# TRV_SX1231_V0_1a.net
KiCad netlist of a schematic drawn in EAGLE
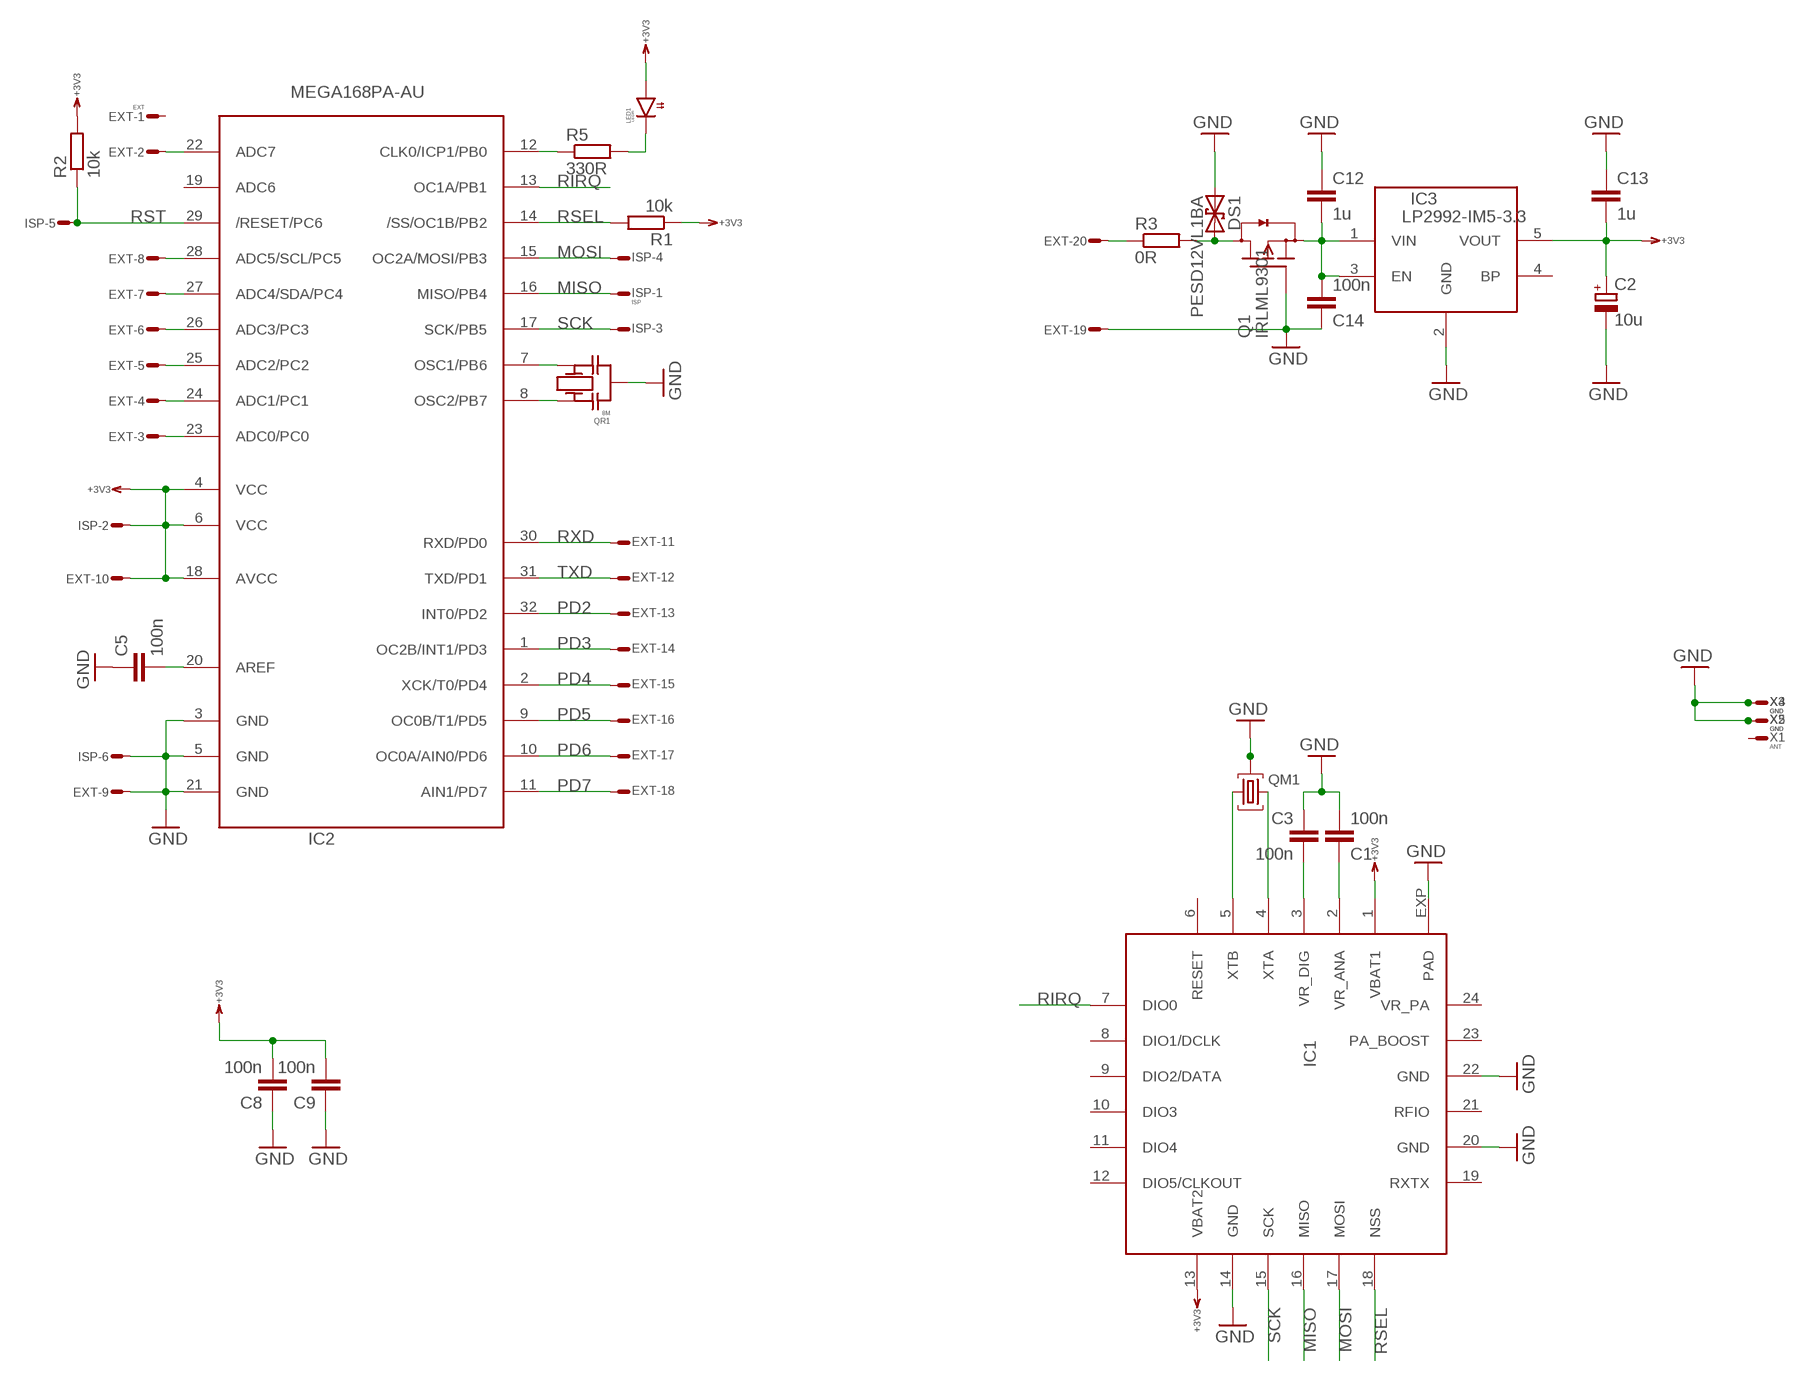
[diagram p0: schematic, sheet 1]

(export (version "E")
  (design (tool "Eeschema 10.0.6"))
  (components
    (comp (ref "C1")
      (value "100n")
      (footprint "eagle-import:0603")
      (libsource (lib "eagle-import") (part "C0603"))
    )
    (comp (ref "C2")
      (value "10u")
      (footprint "eagle-import:SMC_B")
      (libsource (lib "eagle-import") (part "C_POLSMCB"))
    )
    (comp (ref "C3")
      (value "100n")
      (footprint "eagle-import:0603")
      (libsource (lib "eagle-import") (part "C0603"))
    )
    (comp (ref "C5")
      (value "100n")
      (footprint "eagle-import:0603")
      (libsource (lib "eagle-import") (part "C0603"))
    )
    (comp (ref "C8")
      (value "100n")
      (footprint "eagle-import:0603")
      (libsource (lib "eagle-import") (part "C0603"))
    )
    (comp (ref "C9")
      (value "100n")
      (footprint "eagle-import:0603")
      (libsource (lib "eagle-import") (part "C0603"))
    )
    (comp (ref "C12")
      (value "1u")
      (footprint "eagle-import:0603")
      (libsource (lib "eagle-import") (part "C0603"))
    )
    (comp (ref "C13")
      (value "1u")
      (footprint "eagle-import:0603")
      (libsource (lib "eagle-import") (part "C0603"))
    )
    (comp (ref "C14")
      (value "100n")
      (footprint "eagle-import:0603")
      (libsource (lib "eagle-import") (part "C0603"))
    )
    (comp (ref "DS1")
      (value "PESD12VL1BA")
      (footprint "eagle-import:SOD323")
      (libsource (lib "eagle-import") (part "TVS-U323"))
    )
    (comp (ref "EXT")
      (value "EXT")
      (footprint "eagle-import:ML20S")
      (libsource (lib "eagle-import") (part "ML20?ES"))
    )
    (comp (ref "IC1")
      (value "SX1231")
      (footprint "eagle-import:QFN24")
      (libsource (lib "eagle-import") (part "SX1231"))
    )
    (comp (ref "IC2")
      (value "MEGA168PA-AU")
      (footprint "eagle-import:TQFP32-08")
      (libsource (lib "eagle-import") (part "MEGA168PA"))
    )
    (comp (ref "IC3")
      (value "LP2992-IM5-3.3")
      (footprint "eagle-import:SOT23-5")
      (libsource (lib "eagle-import") (part "LDO"))
    )
    (comp (ref "ISP")
      (value "ISP")
      (footprint "eagle-import:ML6S")
      (libsource (lib "eagle-import") (part "ML6ES"))
    )
    (comp (ref "LED1")
      (value "LEDR")
      (footprint "eagle-import:0805")
      (libsource (lib "eagle-import") (part "LED0805"))
    )
    (comp (ref "Q1")
      (value "IRLML9301")
      (footprint "eagle-import:SOT23")
      (libsource (lib "eagle-import") (part "FET-PDSOT23"))
    )
    (comp (ref "QM1")
      (value "QM5X3.2")
      (footprint "eagle-import:ABM3C")
      (libsource (lib "eagle-import") (part "QM5X3.2"))
    )
    (comp (ref "QR1")
      (value "8M")
      (footprint "eagle-import:CR")
      (libsource (lib "eagle-import") (part "QRCR"))
    )
    (comp (ref "R1")
      (value "10k")
      (footprint "eagle-import:0603")
      (libsource (lib "eagle-import") (part "R0603"))
    )
    (comp (ref "R2")
      (value "10k")
      (footprint "eagle-import:0603")
      (libsource (lib "eagle-import") (part "R0603"))
    )
    (comp (ref "R3")
      (value "0R")
      (footprint "eagle-import:0603")
      (libsource (lib "eagle-import") (part "R0603"))
    )
    (comp (ref "R5")
      (value "330R")
      (footprint "eagle-import:0603")
      (libsource (lib "eagle-import") (part "R0603"))
    )
    (comp (ref "X1")
      (value "ANT")
      (footprint "eagle-import:S2.54_1.27")
      (libsource (lib "eagle-import") (part "WIREPADS2.54/1.27"))
    )
    (comp (ref "X2")
      (value "GND")
      (footprint "eagle-import:S2.54_1.27")
      (libsource (lib "eagle-import") (part "WIREPADS2.54/1.27"))
    )
    (comp (ref "X3")
      (value "GND")
      (footprint "eagle-import:S2.54_1.27")
      (libsource (lib "eagle-import") (part "WIREPADS2.54/1.27"))
    )
    (comp (ref "X4")
      (value "GND")
      (footprint "eagle-import:S2.54_1.27")
      (libsource (lib "eagle-import") (part "WIREPADS2.54/1.27"))
    )
    (comp (ref "X5")
      (value "GND")
      (footprint "eagle-import:S2.54_1.27")
      (libsource (lib "eagle-import") (part "WIREPADS2.54/1.27"))
    )
  )
  (nets
    (net (code "1") (name "+3V3") (class "Default")
      (node (ref "C13") (pin "2") (pinfunction "2_2") (pintype "passive"))
      (node (ref "C2") (pin "+") (pinfunction "+_+") (pintype "passive"))
      (node (ref "C8") (pin "2") (pinfunction "2_2") (pintype "passive"))
      (node (ref "C9") (pin "2") (pinfunction "2_2") (pintype "passive"))
      (node (ref "EXT") (pin "10") (pinfunction "S_10") (pintype "passive"))
      (node (ref "IC1") (pin "1") (pinfunction "VBAT1_1") (pintype "bidirectional"))
      (node (ref "IC1") (pin "13") (pinfunction "VBAT2_13") (pintype "bidirectional"))
      (node (ref "IC2") (pin "18") (pinfunction "AVCC_18") (pintype "bidirectional"))
      (node (ref "IC2") (pin "4") (pinfunction "VCC_4") (pintype "bidirectional"))
      (node (ref "IC2") (pin "6") (pinfunction "VCC_6") (pintype "bidirectional"))
      (node (ref "IC3") (pin "5") (pinfunction "VOUT_5") (pintype "bidirectional"))
      (node (ref "ISP") (pin "2") (pinfunction "S_2") (pintype "passive"))
      (node (ref "LED1") (pin "C") (pinfunction "A_C") (pintype "bidirectional"))
      (node (ref "R1") (pin "1") (pinfunction "1_1") (pintype "passive"))
      (node (ref "R2") (pin "2") (pinfunction "2_2") (pintype "passive"))
    )
    (net (code "2") (name "/MISO") (class "Default")
      (node (ref "IC1") (pin "16") (pinfunction "MISO_16") (pintype "output"))
      (node (ref "IC2") (pin "16") (pinfunction "MISO/PB4_16") (pintype "bidirectional"))
      (node (ref "ISP") (pin "1") (pinfunction "S_1") (pintype "passive"))
    )
    (net (code "3") (name "/MOSI") (class "Default")
      (node (ref "IC1") (pin "17") (pinfunction "MOSI_17") (pintype "input"))
      (node (ref "IC2") (pin "15") (pinfunction "OC2A/MOSI/PB3_15") (pintype "bidirectional"))
      (node (ref "ISP") (pin "4") (pinfunction "S_4") (pintype "passive"))
    )
    (net (code "4") (name "/PD2") (class "Default")
      (node (ref "EXT") (pin "13") (pinfunction "S_13") (pintype "passive"))
      (node (ref "IC2") (pin "32") (pinfunction "INT0/PD2_32") (pintype "bidirectional"))
    )
    (net (code "5") (name "/PD3") (class "Default")
      (node (ref "EXT") (pin "14") (pinfunction "S_14") (pintype "passive"))
      (node (ref "IC2") (pin "1") (pinfunction "OC2B/INT1/PD3_1") (pintype "bidirectional"))
    )
    (net (code "6") (name "/PD4") (class "Default")
      (node (ref "EXT") (pin "15") (pinfunction "S_15") (pintype "passive"))
      (node (ref "IC2") (pin "2") (pinfunction "XCK/T0/PD4_2") (pintype "bidirectional"))
    )
    (net (code "7") (name "/PD5") (class "Default")
      (node (ref "EXT") (pin "16") (pinfunction "S_16") (pintype "passive"))
      (node (ref "IC2") (pin "9") (pinfunction "OC0B/T1/PD5_9") (pintype "bidirectional"))
    )
    (net (code "8") (name "/PD6") (class "Default")
      (node (ref "EXT") (pin "17") (pinfunction "S_17") (pintype "passive"))
      (node (ref "IC2") (pin "10") (pinfunction "OC0A/AIN0/PD6_10") (pintype "bidirectional"))
    )
    (net (code "9") (name "/PD7") (class "Default")
      (node (ref "EXT") (pin "18") (pinfunction "S_18") (pintype "passive"))
      (node (ref "IC2") (pin "11") (pinfunction "AIN1/PD7_11") (pintype "bidirectional"))
    )
    (net (code "10") (name "/RIRQ") (class "Default")
      (node (ref "IC1") (pin "7") (pinfunction "DIO0_7") (pintype "bidirectional"))
      (node (ref "IC2") (pin "13") (pinfunction "OC1A/PB1_13") (pintype "bidirectional"))
    )
    (net (code "11") (name "/RSEL") (class "Default")
      (node (ref "IC1") (pin "18") (pinfunction "NSS_18") (pintype "input"))
      (node (ref "IC2") (pin "14") (pinfunction "/SS/OC1B/PB2_14") (pintype "bidirectional"))
      (node (ref "R1") (pin "2") (pinfunction "2_2") (pintype "passive"))
    )
    (net (code "12") (name "/RST") (class "Default")
      (node (ref "IC2") (pin "29") (pinfunction "/RESET/PC6_29") (pintype "bidirectional"))
      (node (ref "ISP") (pin "5") (pinfunction "S_5") (pintype "passive"))
      (node (ref "R2") (pin "1") (pinfunction "1_1") (pintype "passive"))
    )
    (net (code "13") (name "/RXD") (class "Default")
      (node (ref "EXT") (pin "11") (pinfunction "S_11") (pintype "passive"))
      (node (ref "IC2") (pin "30") (pinfunction "RXD/PD0_30") (pintype "bidirectional"))
    )
    (net (code "14") (name "/SCK") (class "Default")
      (node (ref "IC1") (pin "15") (pinfunction "SCK_15") (pintype "input"))
      (node (ref "IC2") (pin "17") (pinfunction "SCK/PB5_17") (pintype "bidirectional"))
      (node (ref "ISP") (pin "3") (pinfunction "S_3") (pintype "passive"))
    )
    (net (code "15") (name "/TXD") (class "Default")
      (node (ref "EXT") (pin "12") (pinfunction "S_12") (pintype "passive"))
      (node (ref "IC2") (pin "31") (pinfunction "TXD/PD1_31") (pintype "bidirectional"))
    )
    (net (code "16") (name "GND") (class "Default")
      (node (ref "C1") (pin "2") (pinfunction "2_2") (pintype "passive"))
      (node (ref "C12") (pin "1") (pinfunction "1_1") (pintype "passive"))
      (node (ref "C13") (pin "1") (pinfunction "1_1") (pintype "passive"))
      (node (ref "C14") (pin "1") (pinfunction "1_1") (pintype "passive"))
      (node (ref "C2") (pin "-") (pinfunction "-_-") (pintype "passive"))
      (node (ref "C3") (pin "1") (pinfunction "1_1") (pintype "passive"))
      (node (ref "C5") (pin "1") (pinfunction "1_1") (pintype "passive"))
      (node (ref "C8") (pin "1") (pinfunction "1_1") (pintype "passive"))
      (node (ref "C9") (pin "1") (pinfunction "1_1") (pintype "passive"))
      (node (ref "DS1") (pin "A") (pinfunction "1_A") (pintype "passive"))
      (node (ref "EXT") (pin "19") (pinfunction "S_19") (pintype "passive"))
      (node (ref "EXT") (pin "9") (pinfunction "S_9") (pintype "passive"))
      (node (ref "IC1") (pin "14") (pinfunction "GND_14") (pintype "bidirectional"))
      (node (ref "IC1") (pin "20") (pinfunction "GND_20") (pintype "bidirectional"))
      (node (ref "IC1") (pin "22") (pinfunction "GND_22") (pintype "bidirectional"))
      (node (ref "IC1") (pin "EXP") (pinfunction "PAD_EXP") (pintype "bidirectional"))
      (node (ref "IC2") (pin "21") (pinfunction "GND_21") (pintype "bidirectional"))
      (node (ref "IC2") (pin "3") (pinfunction "GND_3") (pintype "bidirectional"))
      (node (ref "IC2") (pin "5") (pinfunction "GND_5") (pintype "bidirectional"))
      (node (ref "IC3") (pin "2") (pinfunction "GND_2") (pintype "bidirectional"))
      (node (ref "ISP") (pin "6") (pinfunction "S_6") (pintype "passive"))
      (node (ref "Q1") (pin "1") (pinfunction "G_1") (pintype "passive"))
      (node (ref "QM1") (pin "P$2") (pinfunction "M1_P$2") (pintype "passive"))
      (node (ref "QM1") (pin "P$4") (pinfunction "M2_P$4") (pintype "passive"))
      (node (ref "QR1") (pin "M") (pinfunction "M_M") (pintype "passive"))
      (node (ref "X2") (pin "1") (pinfunction "S_1") (pintype "passive"))
      (node (ref "X3") (pin "1") (pinfunction "S_1") (pintype "passive"))
      (node (ref "X4") (pin "1") (pinfunction "S_1") (pintype "passive"))
      (node (ref "X5") (pin "1") (pinfunction "S_1") (pintype "passive"))
    )
    (net (code "17") (name "Net-(DS1-2)") (class "Default")
      (node (ref "DS1") (pin "C") (pinfunction "2_C") (pintype "passive"))
      (node (ref "Q1") (pin "3") (pinfunction "D_3") (pintype "passive"))
      (node (ref "R3") (pin "2") (pinfunction "2_2") (pintype "passive"))
    )
    (net (code "18") (name "Net-(EXTL-S)") (class "Default")
      (node (ref "EXT") (pin "2") (pinfunction "S_2") (pintype "passive"))
      (node (ref "IC2") (pin "22") (pinfunction "ADC7_22") (pintype "bidirectional"))
    )
    (net (code "19") (name "Net-(EXTM-S)") (class "Default")
      (node (ref "EXT") (pin "20") (pinfunction "S_20") (pintype "passive"))
      (node (ref "R3") (pin "1") (pinfunction "1_1") (pintype "passive"))
    )
    (net (code "20") (name "Net-(EXTN-S)") (class "Default")
      (node (ref "EXT") (pin "3") (pinfunction "S_3") (pintype "passive"))
      (node (ref "IC2") (pin "23") (pinfunction "ADC0/PC0_23") (pintype "bidirectional"))
    )
    (net (code "21") (name "Net-(EXTO-S)") (class "Default")
      (node (ref "EXT") (pin "4") (pinfunction "S_4") (pintype "passive"))
      (node (ref "IC2") (pin "24") (pinfunction "ADC1/PC1_24") (pintype "bidirectional"))
    )
    (net (code "22") (name "Net-(EXTP-S)") (class "Default")
      (node (ref "EXT") (pin "5") (pinfunction "S_5") (pintype "passive"))
      (node (ref "IC2") (pin "25") (pinfunction "ADC2/PC2_25") (pintype "bidirectional"))
    )
    (net (code "23") (name "Net-(EXTQ-S)") (class "Default")
      (node (ref "EXT") (pin "6") (pinfunction "S_6") (pintype "passive"))
      (node (ref "IC2") (pin "26") (pinfunction "ADC3/PC3_26") (pintype "bidirectional"))
    )
    (net (code "24") (name "Net-(EXTR-S)") (class "Default")
      (node (ref "EXT") (pin "7") (pinfunction "S_7") (pintype "passive"))
      (node (ref "IC2") (pin "27") (pinfunction "ADC4/SDA/PC4_27") (pintype "bidirectional"))
    )
    (net (code "25") (name "Net-(EXTS-S)") (class "Default")
      (node (ref "EXT") (pin "8") (pinfunction "S_8") (pintype "passive"))
      (node (ref "IC2") (pin "28") (pinfunction "ADC5/SCL/PC5_28") (pintype "bidirectional"))
    )
    (net (code "26") (name "Net-(IC1-VR_ANA)") (class "Default")
      (node (ref "C1") (pin "1") (pinfunction "1_1") (pintype "passive"))
      (node (ref "IC1") (pin "2") (pinfunction "VR_ANA_2") (pintype "bidirectional"))
    )
    (net (code "27") (name "Net-(IC1-VR_DIG)") (class "Default")
      (node (ref "C3") (pin "2") (pinfunction "2_2") (pintype "passive"))
      (node (ref "IC1") (pin "3") (pinfunction "VR_DIG_3") (pintype "bidirectional"))
    )
    (net (code "28") (name "Net-(IC1-XTA)") (class "Default")
      (node (ref "IC1") (pin "4") (pinfunction "XTA_4") (pintype "bidirectional"))
      (node (ref "QM1") (pin "P$3") (pinfunction "2_P$3") (pintype "passive"))
    )
    (net (code "29") (name "Net-(IC1-XTB)") (class "Default")
      (node (ref "IC1") (pin "5") (pinfunction "XTB_5") (pintype "bidirectional"))
      (node (ref "QM1") (pin "P$1") (pinfunction "1_P$1") (pintype "passive"))
    )
    (net (code "30") (name "Net-(IC2-AREF)") (class "Default")
      (node (ref "C5") (pin "2") (pinfunction "2_2") (pintype "passive"))
      (node (ref "IC2") (pin "20") (pinfunction "AREF_20") (pintype "bidirectional"))
    )
    (net (code "31") (name "Net-(IC2-CLK0{slash}ICP1{slash}PB0)") (class "Default")
      (node (ref "IC2") (pin "12") (pinfunction "CLK0/ICP1/PB0_12") (pintype "bidirectional"))
      (node (ref "R5") (pin "1") (pinfunction "1_1") (pintype "passive"))
    )
    (net (code "32") (name "Net-(IC2-OSC1{slash}PB6)") (class "Default")
      (node (ref "IC2") (pin "7") (pinfunction "OSC1/PB6_7") (pintype "bidirectional"))
      (node (ref "QR1") (pin "2") (pinfunction "2_2") (pintype "passive"))
    )
    (net (code "33") (name "Net-(IC2-OSC2{slash}PB7)") (class "Default")
      (node (ref "IC2") (pin "8") (pinfunction "OSC2/PB7_8") (pintype "bidirectional"))
      (node (ref "QR1") (pin "1") (pinfunction "1_1") (pintype "passive"))
    )
    (net (code "34") (name "Net-(IC3-EN)") (class "Default")
      (node (ref "C12") (pin "2") (pinfunction "2_2") (pintype "passive"))
      (node (ref "C14") (pin "2") (pinfunction "2_2") (pintype "passive"))
      (node (ref "IC3") (pin "1") (pinfunction "VIN_1") (pintype "bidirectional"))
      (node (ref "IC3") (pin "3") (pinfunction "EN_3") (pintype "bidirectional"))
      (node (ref "Q1") (pin "2") (pinfunction "S_2") (pintype "passive"))
    )
    (net (code "35") (name "Net-(LED1-C)") (class "Default")
      (node (ref "LED1") (pin "A") (pinfunction "C_A") (pintype "bidirectional"))
      (node (ref "R5") (pin "2") (pinfunction "2_2") (pintype "passive"))
    )
    (net (code "36") (name "unconnected-(EXTA-S-Pad1)") (class "Default")
      (node (ref "EXT") (pin "1") (pinfunction "S_1") (pintype "passive"))
    )
    (net (code "37") (name "unconnected-(IC1-DIO1{slash}DCLK-Pad8)") (class "Default")
      (node (ref "IC1") (pin "8") (pinfunction "DIO1/DCLK_8") (pintype "bidirectional"))
    )
    (net (code "38") (name "unconnected-(IC1-DIO2{slash}DATA-Pad9)") (class "Default")
      (node (ref "IC1") (pin "9") (pinfunction "DIO2/DATA_9") (pintype "bidirectional"))
    )
    (net (code "39") (name "unconnected-(IC1-DIO3-Pad10)") (class "Default")
      (node (ref "IC1") (pin "10") (pinfunction "DIO3_10") (pintype "bidirectional"))
    )
    (net (code "40") (name "unconnected-(IC1-DIO4-Pad11)") (class "Default")
      (node (ref "IC1") (pin "11") (pinfunction "DIO4_11") (pintype "bidirectional"))
    )
    (net (code "41") (name "unconnected-(IC1-DIO5{slash}CLKOUT-Pad12)") (class "Default")
      (node (ref "IC1") (pin "12") (pinfunction "DIO5/CLKOUT_12") (pintype "bidirectional"))
    )
    (net (code "42") (name "unconnected-(IC1-PA_BOOST-Pad23)") (class "Default")
      (node (ref "IC1") (pin "23") (pinfunction "PA_BOOST_23") (pintype "output"))
    )
    (net (code "43") (name "unconnected-(IC1-RESET-Pad6)") (class "Default")
      (node (ref "IC1") (pin "6") (pinfunction "RESET_6") (pintype "bidirectional"))
    )
    (net (code "44") (name "unconnected-(IC1-RFIO-Pad21)") (class "Default")
      (node (ref "IC1") (pin "21") (pinfunction "RFIO_21") (pintype "bidirectional"))
    )
    (net (code "45") (name "unconnected-(IC1-RXTX-Pad19)") (class "Default")
      (node (ref "IC1") (pin "19") (pinfunction "RXTX_19") (pintype "output"))
    )
    (net (code "46") (name "unconnected-(IC1-VR_PA-Pad24)") (class "Default")
      (node (ref "IC1") (pin "24") (pinfunction "VR_PA_24") (pintype "bidirectional"))
    )
    (net (code "47") (name "unconnected-(IC2-ADC6-Pad19)") (class "Default")
      (node (ref "IC2") (pin "19") (pinfunction "ADC6_19") (pintype "bidirectional"))
    )
    (net (code "48") (name "unconnected-(IC3-BP-Pad4)") (class "Default")
      (node (ref "IC3") (pin "4") (pinfunction "BP_4") (pintype "bidirectional"))
    )
    (net (code "49") (name "unconnected-(X1-S-Pad1)") (class "Default")
      (node (ref "X1") (pin "1") (pinfunction "S_1") (pintype "passive"))
    )
  )
)
